# SparkFun_MMA8452Q-Breakout.net
KiCad netlist of a schematic drawn in EAGLE
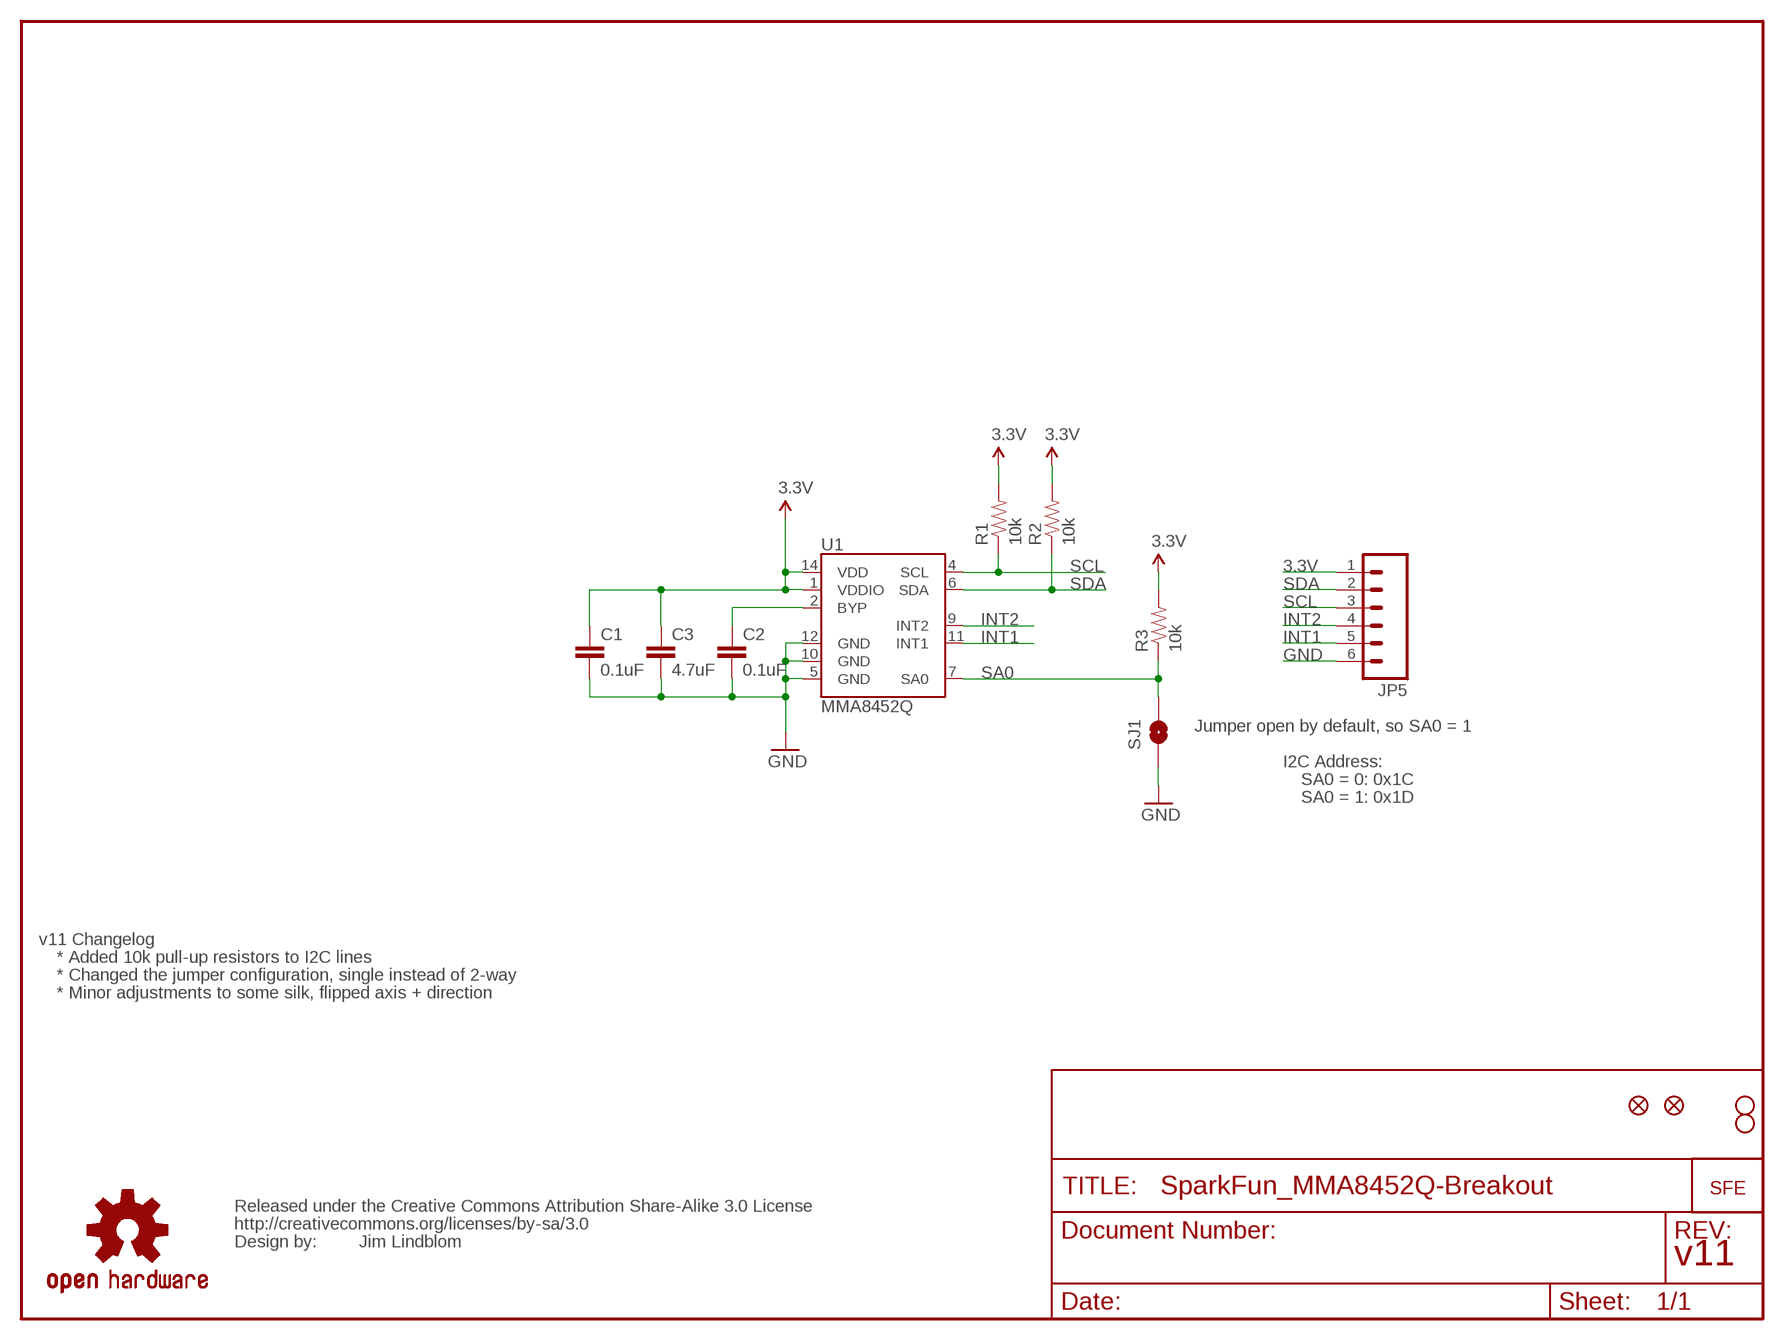
[diagram p0: schematic, sheet 1]

(export (version "E")
  (design (tool "Eeschema 10.0.6"))
  (components
    (comp (ref "C1")
      (value "0.1uF")
      (footprint "eagle-import:0402-CAP")
      (libsource (lib "eagle-import") (part "CAP0402-CAP"))
    )
    (comp (ref "C2")
      (value "0.1uF")
      (footprint "eagle-import:0402-CAP")
      (libsource (lib "eagle-import") (part "CAP0402-CAP"))
    )
    (comp (ref "C3")
      (value "4.7uF")
      (footprint "eagle-import:0402-CAP")
      (libsource (lib "eagle-import") (part "CAP0402-CAP"))
    )
    (comp (ref "JP1")
      (value "LOGO-SFESK")
      (footprint "eagle-import:SFE-LOGO-FLAME")
      (libsource (lib "eagle-import") (part "LOGO-SFESK"))
    )
    (comp (ref "JP2")
      (value "FIDUCIALUFIDUCIAL")
      (footprint "eagle-import:MICRO-FIDUCIAL")
      (libsource (lib "eagle-import") (part "FIDUCIALUFIDUCIAL"))
    )
    (comp (ref "JP3")
      (value "STAND-OFF")
      (footprint "eagle-import:STAND-OFF")
      (libsource (lib "eagle-import") (part "STAND-OFF"))
    )
    (comp (ref "JP4")
      (value "STAND-OFF")
      (footprint "eagle-import:STAND-OFF")
      (libsource (lib "eagle-import") (part "STAND-OFF"))
    )
    (comp (ref "JP5")
      (value "M06SIP")
      (footprint "eagle-import:1X06")
      (libsource (lib "eagle-import") (part "M06SIP"))
    )
    (comp (ref "JP6")
      (value "FIDUCIALUFIDUCIAL")
      (footprint "eagle-import:MICRO-FIDUCIAL")
      (libsource (lib "eagle-import") (part "FIDUCIALUFIDUCIAL"))
    )
    (comp (ref "R1")
      (value "10k")
      (footprint "eagle-import:0402-RES")
      (libsource (lib "eagle-import") (part "RESISTOR0402-RES"))
    )
    (comp (ref "R2")
      (value "10k")
      (footprint "eagle-import:0402-RES")
      (libsource (lib "eagle-import") (part "RESISTOR0402-RES"))
    )
    (comp (ref "R3")
      (value "10k")
      (footprint "eagle-import:0402-RES")
      (libsource (lib "eagle-import") (part "RESISTOR0402-RES"))
    )
    (comp (ref "SJ1")
      (value "SOLDERJUMPERNO")
      (footprint "eagle-import:SJ_2S-NO")
      (libsource (lib "eagle-import") (part "SOLDERJUMPERNO"))
    )
    (comp (ref "U$1")
      (value "OSHW-LOGOS")
      (footprint "eagle-import:OSHW-LOGO-S")
      (libsource (lib "eagle-import") (part "OSHW-LOGOS"))
    )
    (comp (ref "U$2")
      (value "CREATIVE_COMMONS")
      (footprint "eagle-import:CREATIVE_COMMONS")
      (libsource (lib "eagle-import") (part "CREATIVE_COMMONS"))
    )
    (comp (ref "U1")
      (value "MMA8452Q")
      (footprint "eagle-import:QFN-16_0.5MM")
      (libsource (lib "eagle-import") (part "MMA8452Q"))
    )
  )
  (nets
    (net (code "1") (name "/INT1") (class "Default")
      (node (ref "JP5") (pin "5") (pinfunction "5_5") (pintype "passive"))
      (node (ref "U1") (pin "11") (pinfunction "INT1_11") (pintype "bidirectional"))
    )
    (net (code "2") (name "/INT2") (class "Default")
      (node (ref "JP5") (pin "4") (pinfunction "4_4") (pintype "passive"))
      (node (ref "U1") (pin "9") (pinfunction "INT2_9") (pintype "bidirectional"))
    )
    (net (code "3") (name "/SA0") (class "Default")
      (node (ref "R3") (pin "1") (pinfunction "1_1") (pintype "passive"))
      (node (ref "SJ1") (pin "2") (pinfunction "2_2") (pintype "passive"))
      (node (ref "U1") (pin "7") (pinfunction "SA0_7") (pintype "bidirectional"))
    )
    (net (code "4") (name "/SCL") (class "Default")
      (node (ref "JP5") (pin "3") (pinfunction "3_3") (pintype "passive"))
      (node (ref "R1") (pin "1") (pinfunction "1_1") (pintype "passive"))
      (node (ref "U1") (pin "4") (pinfunction "SCL_4") (pintype "bidirectional"))
    )
    (net (code "5") (name "/SDA") (class "Default")
      (node (ref "JP5") (pin "2") (pinfunction "2_2") (pintype "passive"))
      (node (ref "R2") (pin "1") (pinfunction "1_1") (pintype "passive"))
      (node (ref "U1") (pin "6") (pinfunction "SDA_6") (pintype "bidirectional"))
    )
    (net (code "6") (name "3.3V") (class "Default")
      (node (ref "C1") (pin "1") (pinfunction "1_1") (pintype "passive"))
      (node (ref "C3") (pin "1") (pinfunction "1_1") (pintype "passive"))
      (node (ref "JP5") (pin "1") (pinfunction "1_1") (pintype "passive"))
      (node (ref "R1") (pin "2") (pinfunction "2_2") (pintype "passive"))
      (node (ref "R2") (pin "2") (pinfunction "2_2") (pintype "passive"))
      (node (ref "R3") (pin "2") (pinfunction "2_2") (pintype "passive"))
      (node (ref "U1") (pin "1") (pinfunction "VDDIO_1") (pintype "bidirectional"))
      (node (ref "U1") (pin "14") (pinfunction "VDD_14") (pintype "bidirectional"))
    )
    (net (code "7") (name "GND") (class "Default")
      (node (ref "C1") (pin "2") (pinfunction "2_2") (pintype "passive"))
      (node (ref "C2") (pin "2") (pinfunction "2_2") (pintype "passive"))
      (node (ref "C3") (pin "2") (pinfunction "2_2") (pintype "passive"))
      (node (ref "JP5") (pin "6") (pinfunction "6_6") (pintype "passive"))
      (node (ref "SJ1") (pin "1") (pinfunction "1_1") (pintype "passive"))
      (node (ref "U1") (pin "10") (pinfunction "GND_10") (pintype "bidirectional"))
      (node (ref "U1") (pin "12") (pinfunction "GND_12") (pintype "bidirectional"))
      (node (ref "U1") (pin "5") (pinfunction "GND_5") (pintype "bidirectional"))
    )
    (net (code "8") (name "Net-(U1-BYP)") (class "Default")
      (node (ref "C2") (pin "1") (pinfunction "1_1") (pintype "passive"))
      (node (ref "U1") (pin "2") (pinfunction "BYP_2") (pintype "bidirectional"))
    )
  )
)
